# VCA-v2.net
KiCad netlist of a schematic drawn in EAGLE
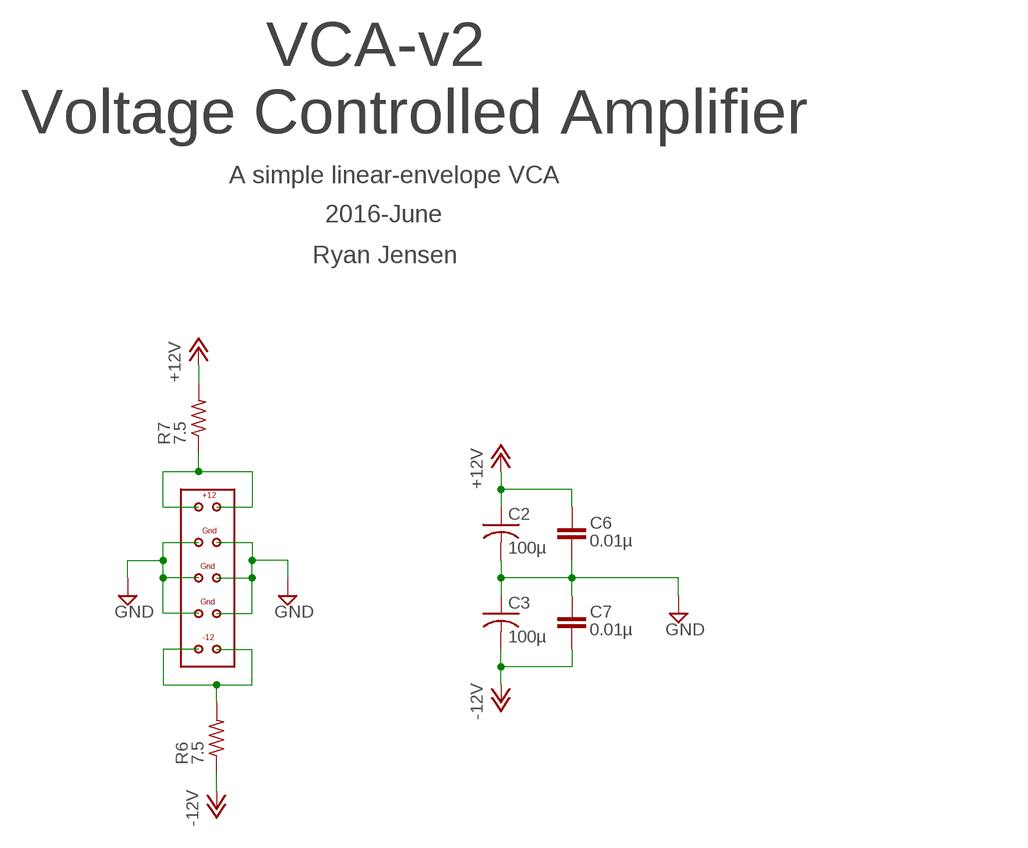
[diagram p0: schematic, sheet 1]
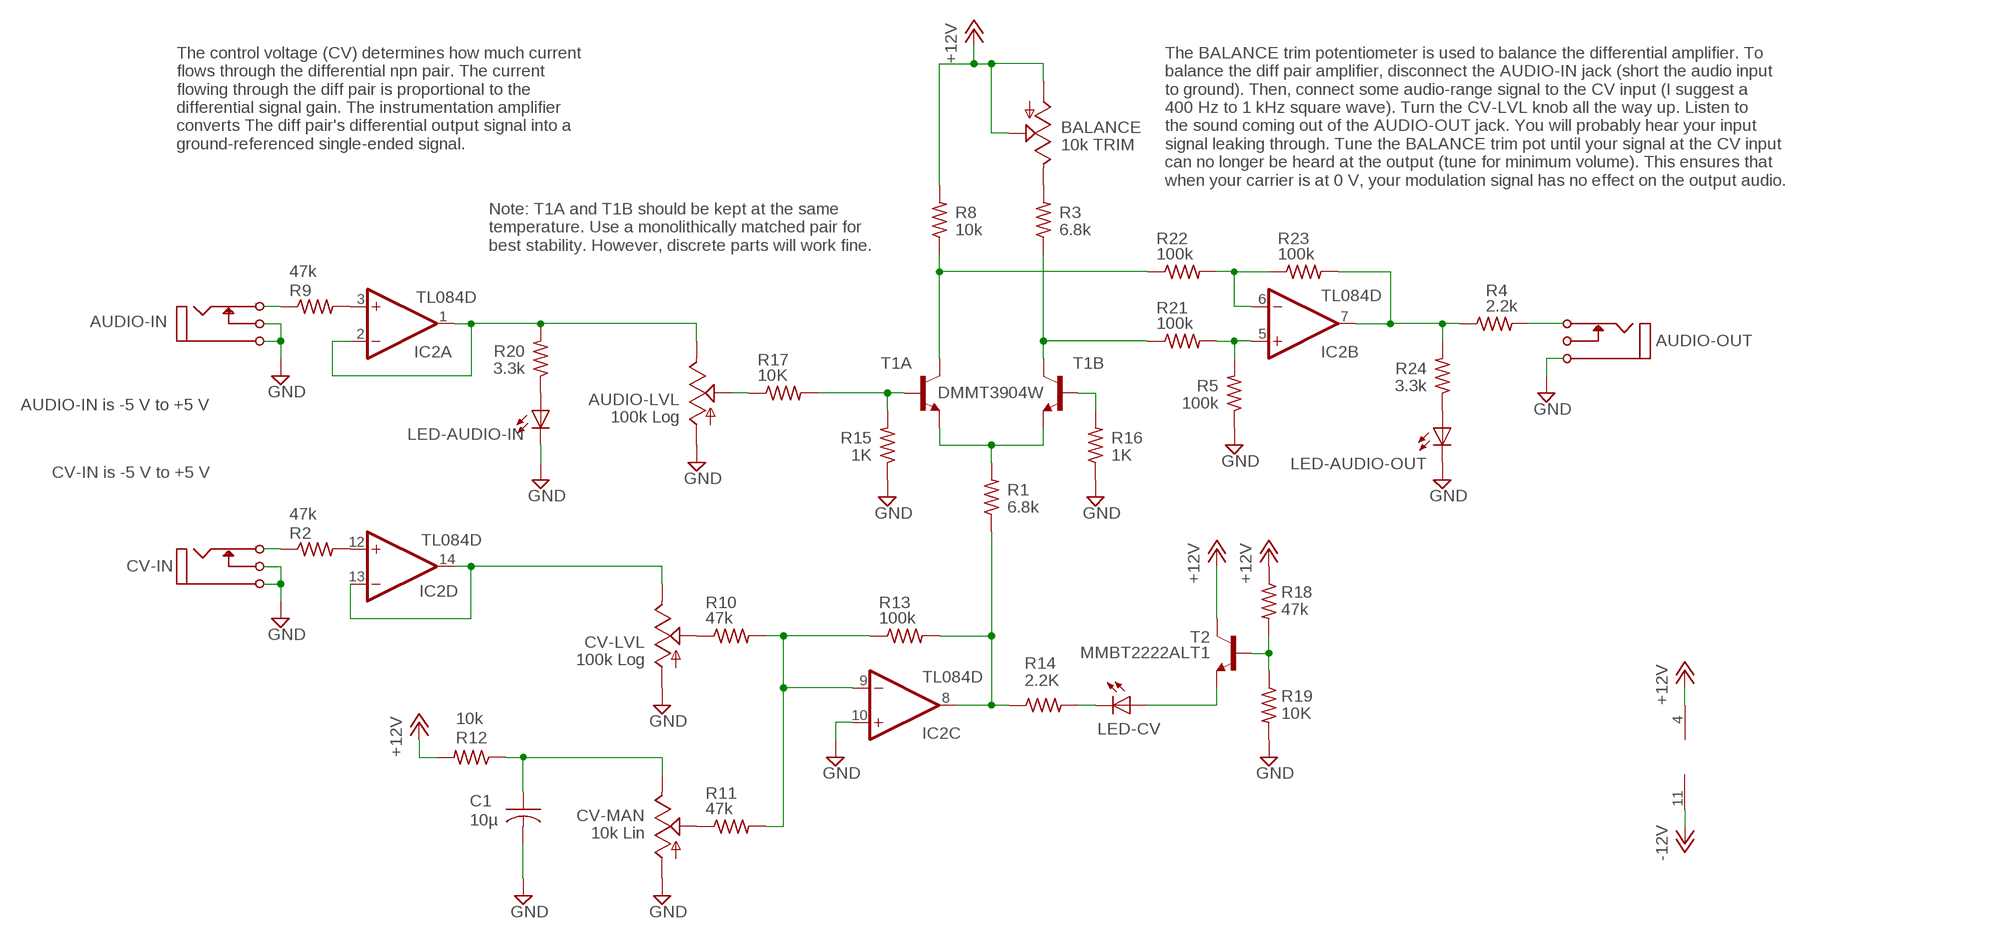
[diagram p1: schematic, sheet 2]

(export (version "E")
  (design (tool "Eeschema 10.0.6"))
  (components
    (comp (ref "C2")
      (value "100µ")
      (footprint "eagle-import:C025-050X050")
      (libsource (lib "eagle-import") (part "C-US025-050X050"))
    )
    (comp (ref "C3")
      (value "100µ")
      (footprint "eagle-import:C025-050X050")
      (libsource (lib "eagle-import") (part "C-US025-050X050"))
    )
    (comp (ref "C6")
      (value "0.01µ")
      (footprint "eagle-import:C0603")
      (libsource (lib "eagle-import") (part "C-EUC0603"))
    )
    (comp (ref "C7")
      (value "0.01µ")
      (footprint "eagle-import:C0603")
      (libsource (lib "eagle-import") (part "C-EUC0603"))
    )
    (comp (ref "R6")
      (value "7.5")
      (footprint "eagle-import:R0603")
      (libsource (lib "eagle-import") (part "R-US_R0603"))
    )
    (comp (ref "R7")
      (value "7.5")
      (footprint "eagle-import:R0603")
      (libsource (lib "eagle-import") (part "R-US_R0603"))
    )
    (comp (ref "U$1")
      (value "EURORACK-POWER")
      (footprint "eagle-import:EURORACK-POWER")
      (libsource (lib "eagle-import") (part "EURORACK-POWER"))
    )
    (comp (ref "AUDIO-IN")
      (value "I/O")
      (footprint "eagle-import:MONO_JACK")
      (libsource (lib "eagle-import") (part "MONO_JACK"))
    )
    (comp (ref "AUDIO-LVL")
      (value "100k Log")
      (footprint "eagle-import:B64Y")
      (libsource (lib "eagle-import") (part "TRIM_US-B64Y"))
    )
    (comp (ref "AUDIO-OUT")
      (value "I/O")
      (footprint "eagle-import:MONO_JACK")
      (libsource (lib "eagle-import") (part "MONO_JACK"))
    )
    (comp (ref "BALANCE")
      (value "10k TRIM")
      (footprint "eagle-import:B64Y")
      (libsource (lib "eagle-import") (part "TRIM_US-B64Y"))
    )
    (comp (ref "C1")
      (value "10µ")
      (footprint "eagle-import:C025-050X050")
      (libsource (lib "eagle-import") (part "C-US025-050X050"))
    )
    (comp (ref "CV-IN")
      (value "I/O")
      (footprint "eagle-import:MONO_JACK")
      (libsource (lib "eagle-import") (part "MONO_JACK"))
    )
    (comp (ref "CV-LVL")
      (value "100k Log")
      (footprint "eagle-import:B64Y")
      (libsource (lib "eagle-import") (part "TRIM_US-B64Y"))
    )
    (comp (ref "CV-MAN")
      (value "10k Lin")
      (footprint "eagle-import:B64Y")
      (libsource (lib "eagle-import") (part "TRIM_US-B64Y"))
    )
    (comp (ref "IC2")
      (value "TL084D")
      (footprint "eagle-import:SO14")
      (libsource (lib "eagle-import") (part "TL084D"))
    )
    (comp (ref "LED-AUDIO-IN")
      (value "TLLG4400")
      (footprint "eagle-import:LED3MM")
      (fields (field (name "MF") "VISHAY SEMICONDUCTOR"))
      (libsource (lib "eagle-import") (part "TLLG4400"))
    )
    (comp (ref "LED-AUDIO-OUT")
      (value "TLLG4400")
      (footprint "eagle-import:LED3MM")
      (fields (field (name "MF") "VISHAY SEMICONDUCTOR"))
      (libsource (lib "eagle-import") (part "TLLG4400"))
    )
    (comp (ref "LED-CV")
      (value "TLLG4400")
      (footprint "eagle-import:LED3MM")
      (fields (field (name "MF") "VISHAY SEMICONDUCTOR"))
      (libsource (lib "eagle-import") (part "TLLG4400"))
    )
    (comp (ref "R1")
      (value "6.8k")
      (footprint "eagle-import:R0603")
      (libsource (lib "eagle-import") (part "R-US_R0603"))
    )
    (comp (ref "R2")
      (value "47k")
      (footprint "eagle-import:R0603")
      (libsource (lib "eagle-import") (part "R-US_R0603"))
    )
    (comp (ref "R3")
      (value "6.8k")
      (footprint "eagle-import:R0603")
      (libsource (lib "eagle-import") (part "R-US_R0603"))
    )
    (comp (ref "R4")
      (value "2.2k")
      (footprint "eagle-import:R0603")
      (libsource (lib "eagle-import") (part "R-US_R0603"))
    )
    (comp (ref "R5")
      (value "100k")
      (footprint "eagle-import:R0603")
      (libsource (lib "eagle-import") (part "R-US_R0603"))
    )
    (comp (ref "R8")
      (value "10k")
      (footprint "eagle-import:R0603")
      (libsource (lib "eagle-import") (part "R-US_R0603"))
    )
    (comp (ref "R9")
      (value "47k")
      (footprint "eagle-import:R0603")
      (libsource (lib "eagle-import") (part "R-US_R0603"))
    )
    (comp (ref "R10")
      (value "47k")
      (footprint "eagle-import:R0603")
      (libsource (lib "eagle-import") (part "R-US_R0603"))
    )
    (comp (ref "R11")
      (value "47k")
      (footprint "eagle-import:R0603")
      (libsource (lib "eagle-import") (part "R-US_R0603"))
    )
    (comp (ref "R12")
      (value "10k")
      (footprint "eagle-import:R0603")
      (libsource (lib "eagle-import") (part "R-US_R0603"))
    )
    (comp (ref "R13")
      (value "100k")
      (footprint "eagle-import:R0603")
      (libsource (lib "eagle-import") (part "R-US_R0603"))
    )
    (comp (ref "R14")
      (value "2.2K")
      (footprint "eagle-import:R0603")
      (libsource (lib "eagle-import") (part "R-US_R0603"))
    )
    (comp (ref "R15")
      (value "1K")
      (footprint "eagle-import:R0603")
      (libsource (lib "eagle-import") (part "R-US_R0603"))
    )
    (comp (ref "R16")
      (value "1K")
      (footprint "eagle-import:R0603")
      (libsource (lib "eagle-import") (part "R-US_R0603"))
    )
    (comp (ref "R17")
      (value "10K")
      (footprint "eagle-import:R0603")
      (libsource (lib "eagle-import") (part "R-US_R0603"))
    )
    (comp (ref "R18")
      (value "47k")
      (footprint "eagle-import:R0603")
      (libsource (lib "eagle-import") (part "R-US_R0603"))
    )
    (comp (ref "R19")
      (value "10K")
      (footprint "eagle-import:R0603")
      (libsource (lib "eagle-import") (part "R-US_R0603"))
    )
    (comp (ref "R20")
      (value "3.3k")
      (footprint "eagle-import:R0603")
      (libsource (lib "eagle-import") (part "R-US_R0603"))
    )
    (comp (ref "R21")
      (value "100k")
      (footprint "eagle-import:R0603")
      (libsource (lib "eagle-import") (part "R-US_R0603"))
    )
    (comp (ref "R22")
      (value "100k")
      (footprint "eagle-import:R0603")
      (libsource (lib "eagle-import") (part "R-US_R0603"))
    )
    (comp (ref "R23")
      (value "100k")
      (footprint "eagle-import:R0603")
      (libsource (lib "eagle-import") (part "R-US_R0603"))
    )
    (comp (ref "R24")
      (value "3.3k")
      (footprint "eagle-import:R0603")
      (libsource (lib "eagle-import") (part "R-US_R0603"))
    )
    (comp (ref "T1")
      (value "DMMT3904W")
      (footprint "eagle-import:SOT363")
      (libsource (lib "eagle-import") (part "DMMT3904W"))
    )
    (comp (ref "T2")
      (value "MMBT2222ALT1")
      (footprint "eagle-import:SOT23-BEC")
      (libsource (lib "eagle-import") (part "-NPN-SOT23-BECMMBT2222ALT1"))
    )
  )
  (nets
    (net (code "1") (name "+12V") (class "Default")
      (node (ref "BALANCE") (pin "A") (pinfunction "A_A") (pintype "passive"))
      (node (ref "BALANCE") (pin "S") (pinfunction "S_S") (pintype "passive"))
      (node (ref "C2") (pin "1") (pinfunction "1_1") (pintype "passive"))
      (node (ref "C6") (pin "1") (pinfunction "1_1") (pintype "passive"))
      (node (ref "IC2") (pin "4") (pinfunction "V+_4") (pintype "power_in"))
      (node (ref "R12") (pin "2") (pinfunction "2_2") (pintype "passive"))
      (node (ref "R18") (pin "1") (pinfunction "1_1") (pintype "passive"))
      (node (ref "R7") (pin "2") (pinfunction "2_2") (pintype "passive"))
      (node (ref "R8") (pin "2") (pinfunction "2_2") (pintype "passive"))
      (node (ref "T2") (pin "C") (pinfunction "C_C") (pintype "passive"))
    )
    (net (code "2") (name "-12V") (class "Default")
      (node (ref "C3") (pin "2") (pinfunction "2_2") (pintype "passive"))
      (node (ref "C7") (pin "2") (pinfunction "2_2") (pintype "passive"))
      (node (ref "IC2") (pin "11") (pinfunction "V-_11") (pintype "power_in"))
      (node (ref "R6") (pin "1") (pinfunction "1_1") (pintype "passive"))
    )
    (net (code "3") (name "GND") (class "Default")
      (node (ref "AUDIO-IN") (pin "P$1") (pinfunction "P$1_P$1") (pintype "bidirectional"))
      (node (ref "AUDIO-IN") (pin "P$3") (pinfunction "P3_P$3") (pintype "bidirectional"))
      (node (ref "AUDIO-LVL") (pin "A") (pinfunction "A_A") (pintype "passive"))
      (node (ref "AUDIO-OUT") (pin "P$1") (pinfunction "P$1_P$1") (pintype "bidirectional"))
      (node (ref "C1") (pin "2") (pinfunction "2_2") (pintype "passive"))
      (node (ref "C2") (pin "2") (pinfunction "2_2") (pintype "passive"))
      (node (ref "C3") (pin "1") (pinfunction "1_1") (pintype "passive"))
      (node (ref "C6") (pin "2") (pinfunction "2_2") (pintype "passive"))
      (node (ref "C7") (pin "1") (pinfunction "1_1") (pintype "passive"))
      (node (ref "CV-IN") (pin "P$1") (pinfunction "P$1_P$1") (pintype "bidirectional"))
      (node (ref "CV-IN") (pin "P$3") (pinfunction "P3_P$3") (pintype "bidirectional"))
      (node (ref "CV-LVL") (pin "A") (pinfunction "A_A") (pintype "passive"))
      (node (ref "CV-MAN") (pin "A") (pinfunction "A_A") (pintype "passive"))
      (node (ref "IC2") (pin "10") (pinfunction "+IN_10") (pintype "input"))
      (node (ref "LED-AUDIO-IN") (pin "K") (pinfunction "C_K") (pintype "passive"))
      (node (ref "LED-AUDIO-OUT") (pin "K") (pinfunction "C_K") (pintype "passive"))
      (node (ref "R15") (pin "1") (pinfunction "1_1") (pintype "passive"))
      (node (ref "R16") (pin "1") (pinfunction "1_1") (pintype "passive"))
      (node (ref "R19") (pin "2") (pinfunction "2_2") (pintype "passive"))
      (node (ref "R5") (pin "1") (pinfunction "1_1") (pintype "passive"))
      (node (ref "U$1") (pin "P$3") (pinfunction "P$3_P$3") (pintype "bidirectional"))
      (node (ref "U$1") (pin "P$4") (pinfunction "P$4_P$4") (pintype "bidirectional"))
      (node (ref "U$1") (pin "P$5") (pinfunction "P$5_P$5") (pintype "bidirectional"))
      (node (ref "U$1") (pin "P$6") (pinfunction "P$6_P$6") (pintype "bidirectional"))
      (node (ref "U$1") (pin "P$7") (pinfunction "P$7_P$7") (pintype "bidirectional"))
      (node (ref "U$1") (pin "P$8") (pinfunction "P$8_P$8") (pintype "bidirectional"))
    )
    (net (code "4") (name "Net-(AUDIO-IN-P2)") (class "Default")
      (node (ref "AUDIO-IN") (pin "P$2") (pinfunction "P2_P$2") (pintype "bidirectional"))
      (node (ref "R9") (pin "1") (pinfunction "1_1") (pintype "passive"))
    )
    (net (code "5") (name "Net-(AUDIO-LVL-PadS)") (class "Default")
      (node (ref "AUDIO-LVL") (pin "S") (pinfunction "S_S") (pintype "passive"))
      (node (ref "R17") (pin "1") (pinfunction "1_1") (pintype "passive"))
    )
    (net (code "6") (name "Net-(AUDIO-OUT-P2)") (class "Default")
      (node (ref "AUDIO-OUT") (pin "P$2") (pinfunction "P2_P$2") (pintype "bidirectional"))
      (node (ref "R4") (pin "2") (pinfunction "2_2") (pintype "passive"))
    )
    (net (code "7") (name "Net-(BALANCE-PadE)") (class "Default")
      (node (ref "BALANCE") (pin "E") (pinfunction "E_E") (pintype "passive"))
      (node (ref "R3") (pin "2") (pinfunction "2_2") (pintype "passive"))
    )
    (net (code "8") (name "Net-(C1-Pad1)") (class "Default")
      (node (ref "C1") (pin "1") (pinfunction "1_1") (pintype "passive"))
      (node (ref "CV-MAN") (pin "E") (pinfunction "E_E") (pintype "passive"))
      (node (ref "R12") (pin "1") (pinfunction "1_1") (pintype "passive"))
    )
    (net (code "9") (name "Net-(CV-IN-P2)") (class "Default")
      (node (ref "CV-IN") (pin "P$2") (pinfunction "P2_P$2") (pintype "bidirectional"))
      (node (ref "R2") (pin "1") (pinfunction "1_1") (pintype "passive"))
    )
    (net (code "10") (name "Net-(CV-LVL-PadS)") (class "Default")
      (node (ref "CV-LVL") (pin "S") (pinfunction "S_S") (pintype "passive"))
      (node (ref "R10") (pin "1") (pinfunction "1_1") (pintype "passive"))
    )
    (net (code "11") (name "Net-(CV-MAN-PadS)") (class "Default")
      (node (ref "CV-MAN") (pin "S") (pinfunction "S_S") (pintype "passive"))
      (node (ref "R11") (pin "1") (pinfunction "1_1") (pintype "passive"))
    )
    (net (code "12") (name "Net-(IC2A-+IN)") (class "Default")
      (node (ref "IC2") (pin "3") (pinfunction "+IN_3") (pintype "input"))
      (node (ref "R9") (pin "2") (pinfunction "2_2") (pintype "passive"))
    )
    (net (code "13") (name "Net-(IC2A--IN)") (class "Default")
      (node (ref "AUDIO-LVL") (pin "E") (pinfunction "E_E") (pintype "passive"))
      (node (ref "IC2") (pin "1") (pinfunction "OUT_1") (pintype "output"))
      (node (ref "IC2") (pin "2") (pinfunction "-IN_2") (pintype "input"))
      (node (ref "R20") (pin "2") (pinfunction "2_2") (pintype "passive"))
    )
    (net (code "14") (name "Net-(IC2B-+IN)") (class "Default")
      (node (ref "IC2") (pin "5") (pinfunction "+IN_5") (pintype "input"))
      (node (ref "R21") (pin "2") (pinfunction "2_2") (pintype "passive"))
      (node (ref "R5") (pin "2") (pinfunction "2_2") (pintype "passive"))
    )
    (net (code "15") (name "Net-(IC2B--IN)") (class "Default")
      (node (ref "IC2") (pin "6") (pinfunction "-IN_6") (pintype "input"))
      (node (ref "R22") (pin "2") (pinfunction "2_2") (pintype "passive"))
      (node (ref "R23") (pin "1") (pinfunction "1_1") (pintype "passive"))
    )
    (net (code "16") (name "Net-(IC2B-OUT)") (class "Default")
      (node (ref "IC2") (pin "7") (pinfunction "OUT_7") (pintype "output"))
      (node (ref "R23") (pin "2") (pinfunction "2_2") (pintype "passive"))
      (node (ref "R24") (pin "2") (pinfunction "2_2") (pintype "passive"))
      (node (ref "R4") (pin "1") (pinfunction "1_1") (pintype "passive"))
    )
    (net (code "17") (name "Net-(IC2C--IN)") (class "Default")
      (node (ref "IC2") (pin "9") (pinfunction "-IN_9") (pintype "input"))
      (node (ref "R10") (pin "2") (pinfunction "2_2") (pintype "passive"))
      (node (ref "R11") (pin "2") (pinfunction "2_2") (pintype "passive"))
      (node (ref "R13") (pin "1") (pinfunction "1_1") (pintype "passive"))
    )
    (net (code "18") (name "Net-(IC2C-OUT)") (class "Default")
      (node (ref "IC2") (pin "8") (pinfunction "OUT_8") (pintype "output"))
      (node (ref "R1") (pin "1") (pinfunction "1_1") (pintype "passive"))
      (node (ref "R13") (pin "2") (pinfunction "2_2") (pintype "passive"))
      (node (ref "R14") (pin "1") (pinfunction "1_1") (pintype "passive"))
    )
    (net (code "19") (name "Net-(IC2D-+IN)") (class "Default")
      (node (ref "IC2") (pin "12") (pinfunction "+IN_12") (pintype "input"))
      (node (ref "R2") (pin "2") (pinfunction "2_2") (pintype "passive"))
    )
    (net (code "20") (name "Net-(IC2D--IN)") (class "Default")
      (node (ref "CV-LVL") (pin "E") (pinfunction "E_E") (pintype "passive"))
      (node (ref "IC2") (pin "13") (pinfunction "-IN_13") (pintype "input"))
      (node (ref "IC2") (pin "14") (pinfunction "OUT_14") (pintype "output"))
    )
    (net (code "21") (name "Net-(LED-AUDIO-IN-PadA)") (class "Default")
      (node (ref "LED-AUDIO-IN") (pin "A") (pinfunction "A_A") (pintype "passive"))
      (node (ref "R20") (pin "1") (pinfunction "1_1") (pintype "passive"))
    )
    (net (code "22") (name "Net-(LED-AUDIO-OUT-PadA)") (class "Default")
      (node (ref "LED-AUDIO-OUT") (pin "A") (pinfunction "A_A") (pintype "passive"))
      (node (ref "R24") (pin "1") (pinfunction "1_1") (pintype "passive"))
    )
    (net (code "23") (name "Net-(LED-CV-C)") (class "Default")
      (node (ref "LED-CV") (pin "K") (pinfunction "C_K") (pintype "passive"))
      (node (ref "R14") (pin "2") (pinfunction "2_2") (pintype "passive"))
    )
    (net (code "24") (name "Net-(LED-CV-PadA)") (class "Default")
      (node (ref "LED-CV") (pin "A") (pinfunction "A_A") (pintype "passive"))
      (node (ref "T2") (pin "E") (pinfunction "E_E") (pintype "passive"))
    )
    (net (code "25") (name "Net-(R6-Pad2)") (class "Default")
      (node (ref "R6") (pin "2") (pinfunction "2_2") (pintype "passive"))
      (node (ref "U$1") (pin "P$10") (pinfunction "P$10_P$10") (pintype "bidirectional"))
      (node (ref "U$1") (pin "P$9") (pinfunction "P$9_P$9") (pintype "bidirectional"))
    )
    (net (code "26") (name "Net-(R7-Pad1)") (class "Default")
      (node (ref "R7") (pin "1") (pinfunction "1_1") (pintype "passive"))
      (node (ref "U$1") (pin "P$1") (pinfunction "P$1_P$1") (pintype "bidirectional"))
      (node (ref "U$1") (pin "P$2") (pinfunction "P$2_P$2") (pintype "bidirectional"))
    )
    (net (code "27") (name "Net-(R18-Pad2)") (class "Default")
      (node (ref "R18") (pin "2") (pinfunction "2_2") (pintype "passive"))
      (node (ref "R19") (pin "1") (pinfunction "1_1") (pintype "passive"))
      (node (ref "T2") (pin "B") (pinfunction "B_B") (pintype "passive"))
    )
    (net (code "28") (name "Net-(T1A-B)") (class "Default")
      (node (ref "R15") (pin "2") (pinfunction "2_2") (pintype "passive"))
      (node (ref "R17") (pin "2") (pinfunction "2_2") (pintype "passive"))
      (node (ref "T1") (pin "1") (pinfunction "B_1") (pintype "passive"))
    )
    (net (code "29") (name "Net-(T1A-C)") (class "Default")
      (node (ref "R22") (pin "1") (pinfunction "1_1") (pintype "passive"))
      (node (ref "R8") (pin "1") (pinfunction "1_1") (pintype "passive"))
      (node (ref "T1") (pin "6") (pinfunction "C_6") (pintype "passive"))
    )
    (net (code "30") (name "Net-(T1A-E)") (class "Default")
      (node (ref "R1") (pin "2") (pinfunction "2_2") (pintype "passive"))
      (node (ref "T1") (pin "4") (pinfunction "E_4") (pintype "passive"))
      (node (ref "T1") (pin "5") (pinfunction "E_5") (pintype "passive"))
    )
    (net (code "31") (name "Net-(T1B-B)") (class "Default")
      (node (ref "R16") (pin "2") (pinfunction "2_2") (pintype "passive"))
      (node (ref "T1") (pin "2") (pinfunction "B_2") (pintype "passive"))
    )
    (net (code "32") (name "Net-(T1B-C)") (class "Default")
      (node (ref "R21") (pin "1") (pinfunction "1_1") (pintype "passive"))
      (node (ref "R3") (pin "1") (pinfunction "1_1") (pintype "passive"))
      (node (ref "T1") (pin "3") (pinfunction "C_3") (pintype "passive"))
    )
    (net (code "33") (name "unconnected-(AUDIO-OUT-P3-PadP$3)") (class "Default")
      (node (ref "AUDIO-OUT") (pin "P$3") (pinfunction "P3_P$3") (pintype "bidirectional"))
    )
  )
)
